# CMSIS_DAP.net
KiCad netlist of a schematic drawn in Altium Designer
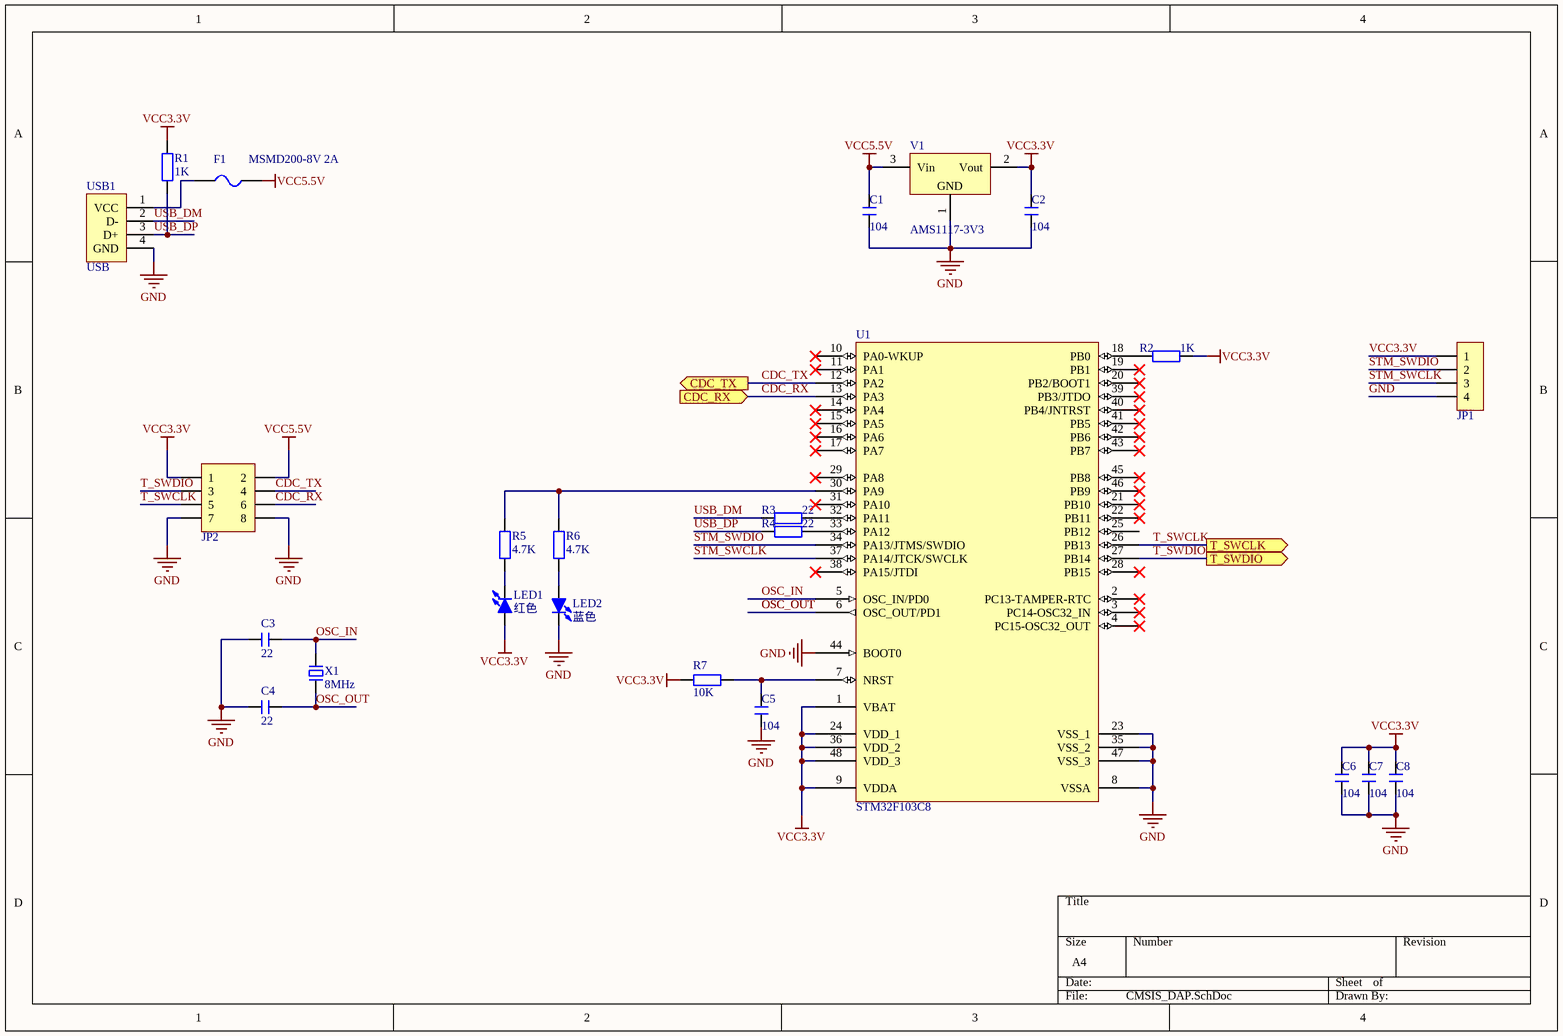
[diagram p0: CMSIS_DAP.SchDoc]

(export (version "E")
  (design (tool "Eeschema 10.0.6"))
  (components
    (comp (ref "C1")
      (value "104")
      (footprint "C 0805_L")
      (description "无极性贴片电容")
      (fields (field (name "版权归属") "源创客"))
      (libsource (lib "3.1   - 电阻-电容-电感") (part "C"))
    )
    (comp (ref "C2")
      (value "104")
      (footprint "C 0805_L")
      (description "无极性贴片电容")
      (fields (field (name "版权归属") "源创客"))
      (libsource (lib "3.1   - 电阻-电容-电感") (part "C"))
    )
    (comp (ref "C3")
      (value "22")
      (footprint "C 0402_L")
      (description "无极性贴片电容")
      (fields (field (name "版权归属") "源创客"))
      (libsource (lib "3.1   - 电阻-电容-电感") (part "C"))
    )
    (comp (ref "C4")
      (value "22")
      (footprint "C 0402_L")
      (description "无极性贴片电容")
      (fields (field (name "版权归属") "源创客"))
      (libsource (lib "3.1   - 电阻-电容-电感") (part "C"))
    )
    (comp (ref "C5")
      (value "104")
      (footprint "C 0603_L")
      (description "无极性贴片电容")
      (fields (field (name "版权归属") "源创客"))
      (libsource (lib "3.1   - 电阻-电容-电感") (part "C"))
    )
    (comp (ref "C6")
      (value "104")
      (footprint "C 0603_L")
      (description "无极性贴片电容")
      (fields (field (name "版权归属") "源创客"))
      (libsource (lib "3.1   - 电阻-电容-电感") (part "C"))
    )
    (comp (ref "C7")
      (value "104")
      (footprint "C 0603_L")
      (description "无极性贴片电容")
      (fields (field (name "版权归属") "源创客"))
      (libsource (lib "3.1   - 电阻-电容-电感") (part "C"))
    )
    (comp (ref "C8")
      (value "104")
      (footprint "C 0603_L")
      (description "无极性贴片电容")
      (fields (field (name "版权归属") "源创客"))
      (libsource (lib "3.1   - 电阻-电容-电感") (part "C"))
    )
    (comp (ref "F1")
      (value "MSMD200-8V 2A")
      (footprint "FU 0805")
      (description "贴片保险丝")
      (fields (field (name "版权归属") "源创客"))
      (libsource (lib "10.1 - 保险丝-晶振") (part "FU"))
    )
    (comp (ref "JP1")
      (value "HDR-1X4")
      (footprint "HDR2.54-LI-4P")
      (description "4P接插件")
      (fields (field (name "版权归属") "源创客"))
      (libsource (lib "4.5   - 接插件-脚距2.54") (part "Header 4"))
    )
    (comp (ref "JP2")
      (value "Header 4X2")
      (footprint "PCBComponent_1")
      (description "4*2P接插件")
      (fields (field (name "版权归属") "源创客"))
      (libsource (lib "4.5   - 接插件-脚距2.54") (part "Header 4X2"))
    )
    (comp (ref "LED1")
      (value "红色")
      (footprint "LED 0603R")
      (description "贴片LED")
      (fields (field (name "版权归属") "源创客"))
      (libsource (lib "LED") (part "LED-SMD"))
    )
    (comp (ref "LED2")
      (value "蓝色")
      (footprint "LED 0603R")
      (description "贴片LED")
      (fields (field (name "版权归属") "源创客"))
      (libsource (lib "LED") (part "LED-SMD"))
    )
    (comp (ref "R1")
      (value "1K")
      (footprint "R 0603_L")
      (description "贴片电阻")
      (fields (field (name "版权归属") "源创客"))
      (libsource (lib "3.1   - 电阻-电容-电感") (part "R"))
    )
    (comp (ref "R2")
      (value "1K")
      (footprint "R 0603_L")
      (description "贴片电阻")
      (fields (field (name "版权归属") "源创客"))
      (libsource (lib "3.1   - 电阻-电容-电感") (part "R"))
    )
    (comp (ref "R3")
      (value "22")
      (footprint "R 0603_L")
      (description "贴片电阻")
      (fields (field (name "版权归属") "源创客"))
      (libsource (lib "3.1   - 电阻-电容-电感") (part "R"))
    )
    (comp (ref "R4")
      (value "22")
      (footprint "R 0603_L")
      (description "贴片电阻")
      (fields (field (name "版权归属") "源创客"))
      (libsource (lib "3.1   - 电阻-电容-电感") (part "R"))
    )
    (comp (ref "R5")
      (value "4.7K")
      (footprint "R 0603_L")
      (description "贴片电阻")
      (fields (field (name "版权归属") "源创客"))
      (libsource (lib "3.1   - 电阻-电容-电感") (part "R"))
    )
    (comp (ref "R6")
      (value "4.7K")
      (footprint "R 0603_L")
      (description "贴片电阻")
      (fields (field (name "版权归属") "源创客"))
      (libsource (lib "3.1   - 电阻-电容-电感") (part "R"))
    )
    (comp (ref "R7")
      (value "10K")
      (footprint "R 0603_L")
      (description "贴片电阻")
      (fields (field (name "版权归属") "源创客"))
      (libsource (lib "3.1   - 电阻-电容-电感") (part "R"))
    )
    (comp (ref "U1")
      (value "STM32F103C8")
      (footprint "LQFP48 7X7_M")
      (description "Flaah:64/RAM:20/IO:36")
      (fields (field (name "版权归属") "源创客"))
      (libsource (lib "2.1   - STM32系列单片机") (part "STM32F103C8"))
    )
    (comp (ref "USB1")
      (value "USB")
      (footprint "USB_A/P_A")
      (description "USB-A型公接口")
      (fields (field (name "版权归属") "源创客"))
      (libsource (lib "接口类") (part "USB-A/P"))
    )
    (comp (ref "V1")
      (value "AMS1117-3V3")
      (footprint "SOT89_L")
      (description "三端稳压芯片")
      (fields (field (name "版权归属") "源创客"))
      (libsource (lib "1.3   - 电源类芯片") (part "AMS1117"))
    )
    (comp (ref "X1")
      (value "8MHz")
      (footprint "OSC 5032-2P")
      (description "2脚无源脚晶振")
      (fields (field (name "版权归属") "源创客"))
      (libsource (lib "10.1 - 保险丝-晶振") (part "XTAL-2P"))
    )
  )
  (nets
    (net (code "1") (name "/CDC_RX") (class "Default")
      (node (ref "JP2") (pin "6") (pinfunction "6_6") (pintype "passive"))
      (node (ref "U1") (pin "13") (pinfunction "PA3_13") (pintype "bidirectional"))
    )
    (net (code "2") (name "/CDC_TX") (class "Default")
      (node (ref "JP2") (pin "4") (pinfunction "4_4") (pintype "passive"))
      (node (ref "U1") (pin "12") (pinfunction "PA2_12") (pintype "bidirectional"))
    )
    (net (code "3") (name "/OSC_IN") (class "Default")
      (node (ref "C3") (pin "2") (pinfunction "2_2") (pintype "passive"))
      (node (ref "U1") (pin "5") (pinfunction "OSC_IN/PD0_5") (pintype "input"))
      (node (ref "X1") (pin "2") (pinfunction "2_2") (pintype "passive"))
    )
    (net (code "4") (name "/OSC_OUT") (class "Default")
      (node (ref "C4") (pin "2") (pinfunction "2_2") (pintype "passive"))
      (node (ref "U1") (pin "6") (pinfunction "OSC_OUT/PD1_6") (pintype "output"))
      (node (ref "X1") (pin "1") (pinfunction "1_1") (pintype "passive"))
    )
    (net (code "5") (name "/STM_SWCLK") (class "Default")
      (node (ref "JP1") (pin "3") (pinfunction "3_3") (pintype "passive"))
      (node (ref "U1") (pin "37") (pinfunction "PA14/JTCK/SWCLK_37") (pintype "bidirectional"))
    )
    (net (code "6") (name "/STM_SWDIO") (class "Default")
      (node (ref "JP1") (pin "2") (pinfunction "2_2") (pintype "passive"))
      (node (ref "U1") (pin "34") (pinfunction "PA13/JTMS/SWDIO_34") (pintype "bidirectional"))
    )
    (net (code "7") (name "/T_SWCLK") (class "Default")
      (node (ref "JP2") (pin "5") (pinfunction "5_5") (pintype "passive"))
      (node (ref "U1") (pin "26") (pinfunction "PB13_26") (pintype "bidirectional"))
    )
    (net (code "8") (name "/T_SWDIO") (class "Default")
      (node (ref "JP2") (pin "3") (pinfunction "3_3") (pintype "passive"))
      (node (ref "U1") (pin "27") (pinfunction "PB14_27") (pintype "bidirectional"))
    )
    (net (code "9") (name "/USB_DM") (class "Default")
      (node (ref "R3") (pin "2") (pinfunction "2_2") (pintype "passive"))
      (node (ref "USB1") (pin "2") (pinfunction "D-_2") (pintype "passive"))
    )
    (net (code "10") (name "/USB_DP") (class "Default")
      (node (ref "R1") (pin "2") (pinfunction "2_2") (pintype "passive"))
      (node (ref "R4") (pin "2") (pinfunction "2_2") (pintype "passive"))
      (node (ref "USB1") (pin "3") (pinfunction "D+_3") (pintype "passive"))
    )
    (net (code "11") (name "GND") (class "Default")
      (node (ref "C1") (pin "2") (pinfunction "2_2") (pintype "passive"))
      (node (ref "C2") (pin "2") (pinfunction "2_2") (pintype "passive"))
      (node (ref "C3") (pin "1") (pinfunction "1_1") (pintype "passive"))
      (node (ref "C4") (pin "1") (pinfunction "1_1") (pintype "passive"))
      (node (ref "C5") (pin "2") (pinfunction "2_2") (pintype "passive"))
      (node (ref "C6") (pin "2") (pinfunction "2_2") (pintype "passive"))
      (node (ref "C7") (pin "2") (pinfunction "2_2") (pintype "passive"))
      (node (ref "C8") (pin "2") (pinfunction "2_2") (pintype "passive"))
      (node (ref "JP1") (pin "4") (pinfunction "4_4") (pintype "passive"))
      (node (ref "JP2") (pin "7") (pinfunction "7_7") (pintype "passive"))
      (node (ref "JP2") (pin "8") (pinfunction "8_8") (pintype "passive"))
      (node (ref "LED2") (pin "2") (pinfunction "K_2") (pintype "passive"))
      (node (ref "U1") (pin "23") (pinfunction "VSS_1_23") (pintype "power_in"))
      (node (ref "U1") (pin "35") (pinfunction "VSS_2_35") (pintype "power_in"))
      (node (ref "U1") (pin "44") (pinfunction "BOOT0_44") (pintype "input"))
      (node (ref "U1") (pin "47") (pinfunction "VSS_3_47") (pintype "power_in"))
      (node (ref "U1") (pin "8") (pinfunction "VSSA_8") (pintype "power_in"))
      (node (ref "USB1") (pin "4") (pinfunction "GND_4") (pintype "passive"))
      (node (ref "V1") (pin "1") (pinfunction "GND_1") (pintype "passive"))
    )
    (net (code "12") (name "Net-(LED1-K)") (class "Default")
      (node (ref "LED1") (pin "2") (pinfunction "K_2") (pintype "passive"))
      (node (ref "R5") (pin "1") (pinfunction "1_1") (pintype "passive"))
    )
    (net (code "13") (name "Net-(LED2-A)") (class "Default")
      (node (ref "LED2") (pin "1") (pinfunction "A_1") (pintype "passive"))
      (node (ref "R6") (pin "1") (pinfunction "1_1") (pintype "passive"))
    )
    (net (code "14") (name "Net-(U1-NRST)") (class "Default")
      (node (ref "C5") (pin "1") (pinfunction "1_1") (pintype "passive"))
      (node (ref "R7") (pin "1") (pinfunction "1_1") (pintype "passive"))
      (node (ref "U1") (pin "7") (pinfunction "NRST_7") (pintype "bidirectional"))
    )
    (net (code "15") (name "Net-(U1-PA9)") (class "Default")
      (node (ref "R5") (pin "2") (pinfunction "2_2") (pintype "passive"))
      (node (ref "R6") (pin "2") (pinfunction "2_2") (pintype "passive"))
      (node (ref "U1") (pin "30") (pinfunction "PA9_30") (pintype "bidirectional"))
    )
    (net (code "16") (name "Net-(U1-PA11)") (class "Default")
      (node (ref "R3") (pin "1") (pinfunction "1_1") (pintype "passive"))
      (node (ref "U1") (pin "32") (pinfunction "PA11_32") (pintype "bidirectional"))
    )
    (net (code "17") (name "Net-(U1-PA12)") (class "Default")
      (node (ref "R4") (pin "1") (pinfunction "1_1") (pintype "passive"))
      (node (ref "U1") (pin "33") (pinfunction "PA12_33") (pintype "bidirectional"))
    )
    (net (code "18") (name "Net-(U1-PB0)") (class "Default")
      (node (ref "R2") (pin "2") (pinfunction "2_2") (pintype "passive"))
      (node (ref "U1") (pin "18") (pinfunction "PB0_18") (pintype "bidirectional"))
    )
    (net (code "19") (name "Net-(USB1-VCC)") (class "Default")
      (node (ref "F1") (pin "1") (pinfunction "1_1") (pintype "passive"))
      (node (ref "USB1") (pin "1") (pinfunction "VCC_1") (pintype "passive"))
    )
    (net (code "20") (name "VCC3.3V") (class "Default")
      (node (ref "C2") (pin "1") (pinfunction "1_1") (pintype "passive"))
      (node (ref "C6") (pin "1") (pinfunction "1_1") (pintype "passive"))
      (node (ref "C7") (pin "1") (pinfunction "1_1") (pintype "passive"))
      (node (ref "C8") (pin "1") (pinfunction "1_1") (pintype "passive"))
      (node (ref "JP1") (pin "1") (pinfunction "1_1") (pintype "passive"))
      (node (ref "JP2") (pin "1") (pinfunction "1_1") (pintype "passive"))
      (node (ref "LED1") (pin "1") (pinfunction "A_1") (pintype "passive"))
      (node (ref "R1") (pin "1") (pinfunction "1_1") (pintype "passive"))
      (node (ref "R2") (pin "1") (pinfunction "1_1") (pintype "passive"))
      (node (ref "R7") (pin "2") (pinfunction "2_2") (pintype "passive"))
      (node (ref "U1") (pin "1") (pinfunction "VBAT_1") (pintype "power_in"))
      (node (ref "U1") (pin "24") (pinfunction "VDD_1_24") (pintype "power_in"))
      (node (ref "U1") (pin "36") (pinfunction "VDD_2_36") (pintype "power_in"))
      (node (ref "U1") (pin "48") (pinfunction "VDD_3_48") (pintype "power_in"))
      (node (ref "U1") (pin "9") (pinfunction "VDDA_9") (pintype "power_in"))
      (node (ref "V1") (pin "2") (pinfunction "Vout_2") (pintype "passive"))
    )
    (net (code "21") (name "VCC5.5V") (class "Default")
      (node (ref "C1") (pin "1") (pinfunction "1_1") (pintype "passive"))
      (node (ref "F1") (pin "2") (pinfunction "2_2") (pintype "passive"))
      (node (ref "JP2") (pin "2") (pinfunction "2_2") (pintype "passive"))
      (node (ref "V1") (pin "3") (pinfunction "Vin_3") (pintype "passive"))
    )
    (net (code "22") (name "unconnected-(U1-PA0-WKUP-Pad10)") (class "Default")
      (node (ref "U1") (pin "10") (pinfunction "PA0-WKUP_10") (pintype "bidirectional+no_connect"))
    )
    (net (code "23") (name "unconnected-(U1-PA1-Pad11)") (class "Default")
      (node (ref "U1") (pin "11") (pinfunction "PA1_11") (pintype "bidirectional+no_connect"))
    )
    (net (code "24") (name "unconnected-(U1-PA4-Pad14)") (class "Default")
      (node (ref "U1") (pin "14") (pinfunction "PA4_14") (pintype "bidirectional+no_connect"))
    )
    (net (code "25") (name "unconnected-(U1-PA5-Pad15)") (class "Default")
      (node (ref "U1") (pin "15") (pinfunction "PA5_15") (pintype "bidirectional+no_connect"))
    )
    (net (code "26") (name "unconnected-(U1-PA6-Pad16)") (class "Default")
      (node (ref "U1") (pin "16") (pinfunction "PA6_16") (pintype "bidirectional+no_connect"))
    )
    (net (code "27") (name "unconnected-(U1-PA7-Pad17)") (class "Default")
      (node (ref "U1") (pin "17") (pinfunction "PA7_17") (pintype "bidirectional+no_connect"))
    )
    (net (code "28") (name "unconnected-(U1-PA8-Pad29)") (class "Default")
      (node (ref "U1") (pin "29") (pinfunction "PA8_29") (pintype "bidirectional+no_connect"))
    )
    (net (code "29") (name "unconnected-(U1-PA10-Pad31)") (class "Default")
      (node (ref "U1") (pin "31") (pinfunction "PA10_31") (pintype "bidirectional+no_connect"))
    )
    (net (code "30") (name "unconnected-(U1-PA15{slash}JTDI-Pad38)") (class "Default")
      (node (ref "U1") (pin "38") (pinfunction "PA15/JTDI_38") (pintype "bidirectional+no_connect"))
    )
    (net (code "31") (name "unconnected-(U1-PB1-Pad19)") (class "Default")
      (node (ref "U1") (pin "19") (pinfunction "PB1_19") (pintype "bidirectional+no_connect"))
    )
    (net (code "32") (name "unconnected-(U1-PB2{slash}BOOT1-Pad20)") (class "Default")
      (node (ref "U1") (pin "20") (pinfunction "PB2/BOOT1_20") (pintype "bidirectional+no_connect"))
    )
    (net (code "33") (name "unconnected-(U1-PB3{slash}JTDO-Pad39)") (class "Default")
      (node (ref "U1") (pin "39") (pinfunction "PB3/JTDO_39") (pintype "bidirectional+no_connect"))
    )
    (net (code "34") (name "unconnected-(U1-PB4{slash}JNTRST-Pad40)") (class "Default")
      (node (ref "U1") (pin "40") (pinfunction "PB4/JNTRST_40") (pintype "bidirectional+no_connect"))
    )
    (net (code "35") (name "unconnected-(U1-PB5-Pad41)") (class "Default")
      (node (ref "U1") (pin "41") (pinfunction "PB5_41") (pintype "bidirectional+no_connect"))
    )
    (net (code "36") (name "unconnected-(U1-PB6-Pad42)") (class "Default")
      (node (ref "U1") (pin "42") (pinfunction "PB6_42") (pintype "bidirectional+no_connect"))
    )
    (net (code "37") (name "unconnected-(U1-PB7-Pad43)") (class "Default")
      (node (ref "U1") (pin "43") (pinfunction "PB7_43") (pintype "bidirectional+no_connect"))
    )
    (net (code "38") (name "unconnected-(U1-PB8-Pad45)") (class "Default")
      (node (ref "U1") (pin "45") (pinfunction "PB8_45") (pintype "bidirectional+no_connect"))
    )
    (net (code "39") (name "unconnected-(U1-PB9-Pad46)") (class "Default")
      (node (ref "U1") (pin "46") (pinfunction "PB9_46") (pintype "bidirectional+no_connect"))
    )
    (net (code "40") (name "unconnected-(U1-PB10-Pad21)") (class "Default")
      (node (ref "U1") (pin "21") (pinfunction "PB10_21") (pintype "bidirectional+no_connect"))
    )
    (net (code "41") (name "unconnected-(U1-PB11-Pad22)") (class "Default")
      (node (ref "U1") (pin "22") (pinfunction "PB11_22") (pintype "bidirectional+no_connect"))
    )
    (net (code "42") (name "unconnected-(U1-PB12-Pad25)") (class "Default")
      (node (ref "U1") (pin "25") (pinfunction "PB12_25") (pintype "bidirectional"))
    )
    (net (code "43") (name "unconnected-(U1-PB15-Pad28)") (class "Default")
      (node (ref "U1") (pin "28") (pinfunction "PB15_28") (pintype "bidirectional+no_connect"))
    )
    (net (code "44") (name "unconnected-(U1-PC13-TAMPER-RTC-Pad2)") (class "Default")
      (node (ref "U1") (pin "2") (pinfunction "PC13-TAMPER-RTC_2") (pintype "bidirectional+no_connect"))
    )
    (net (code "45") (name "unconnected-(U1-PC14-OSC32_IN-Pad3)") (class "Default")
      (node (ref "U1") (pin "3") (pinfunction "PC14-OSC32_IN_3") (pintype "bidirectional+no_connect"))
    )
    (net (code "46") (name "unconnected-(U1-PC15-OSC32_OUT-Pad4)") (class "Default")
      (node (ref "U1") (pin "4") (pinfunction "PC15-OSC32_OUT_4") (pintype "bidirectional+no_connect"))
    )
  )
)
